# Connector_0.net
KiCad netlist of a schematic drawn in Altium Designer
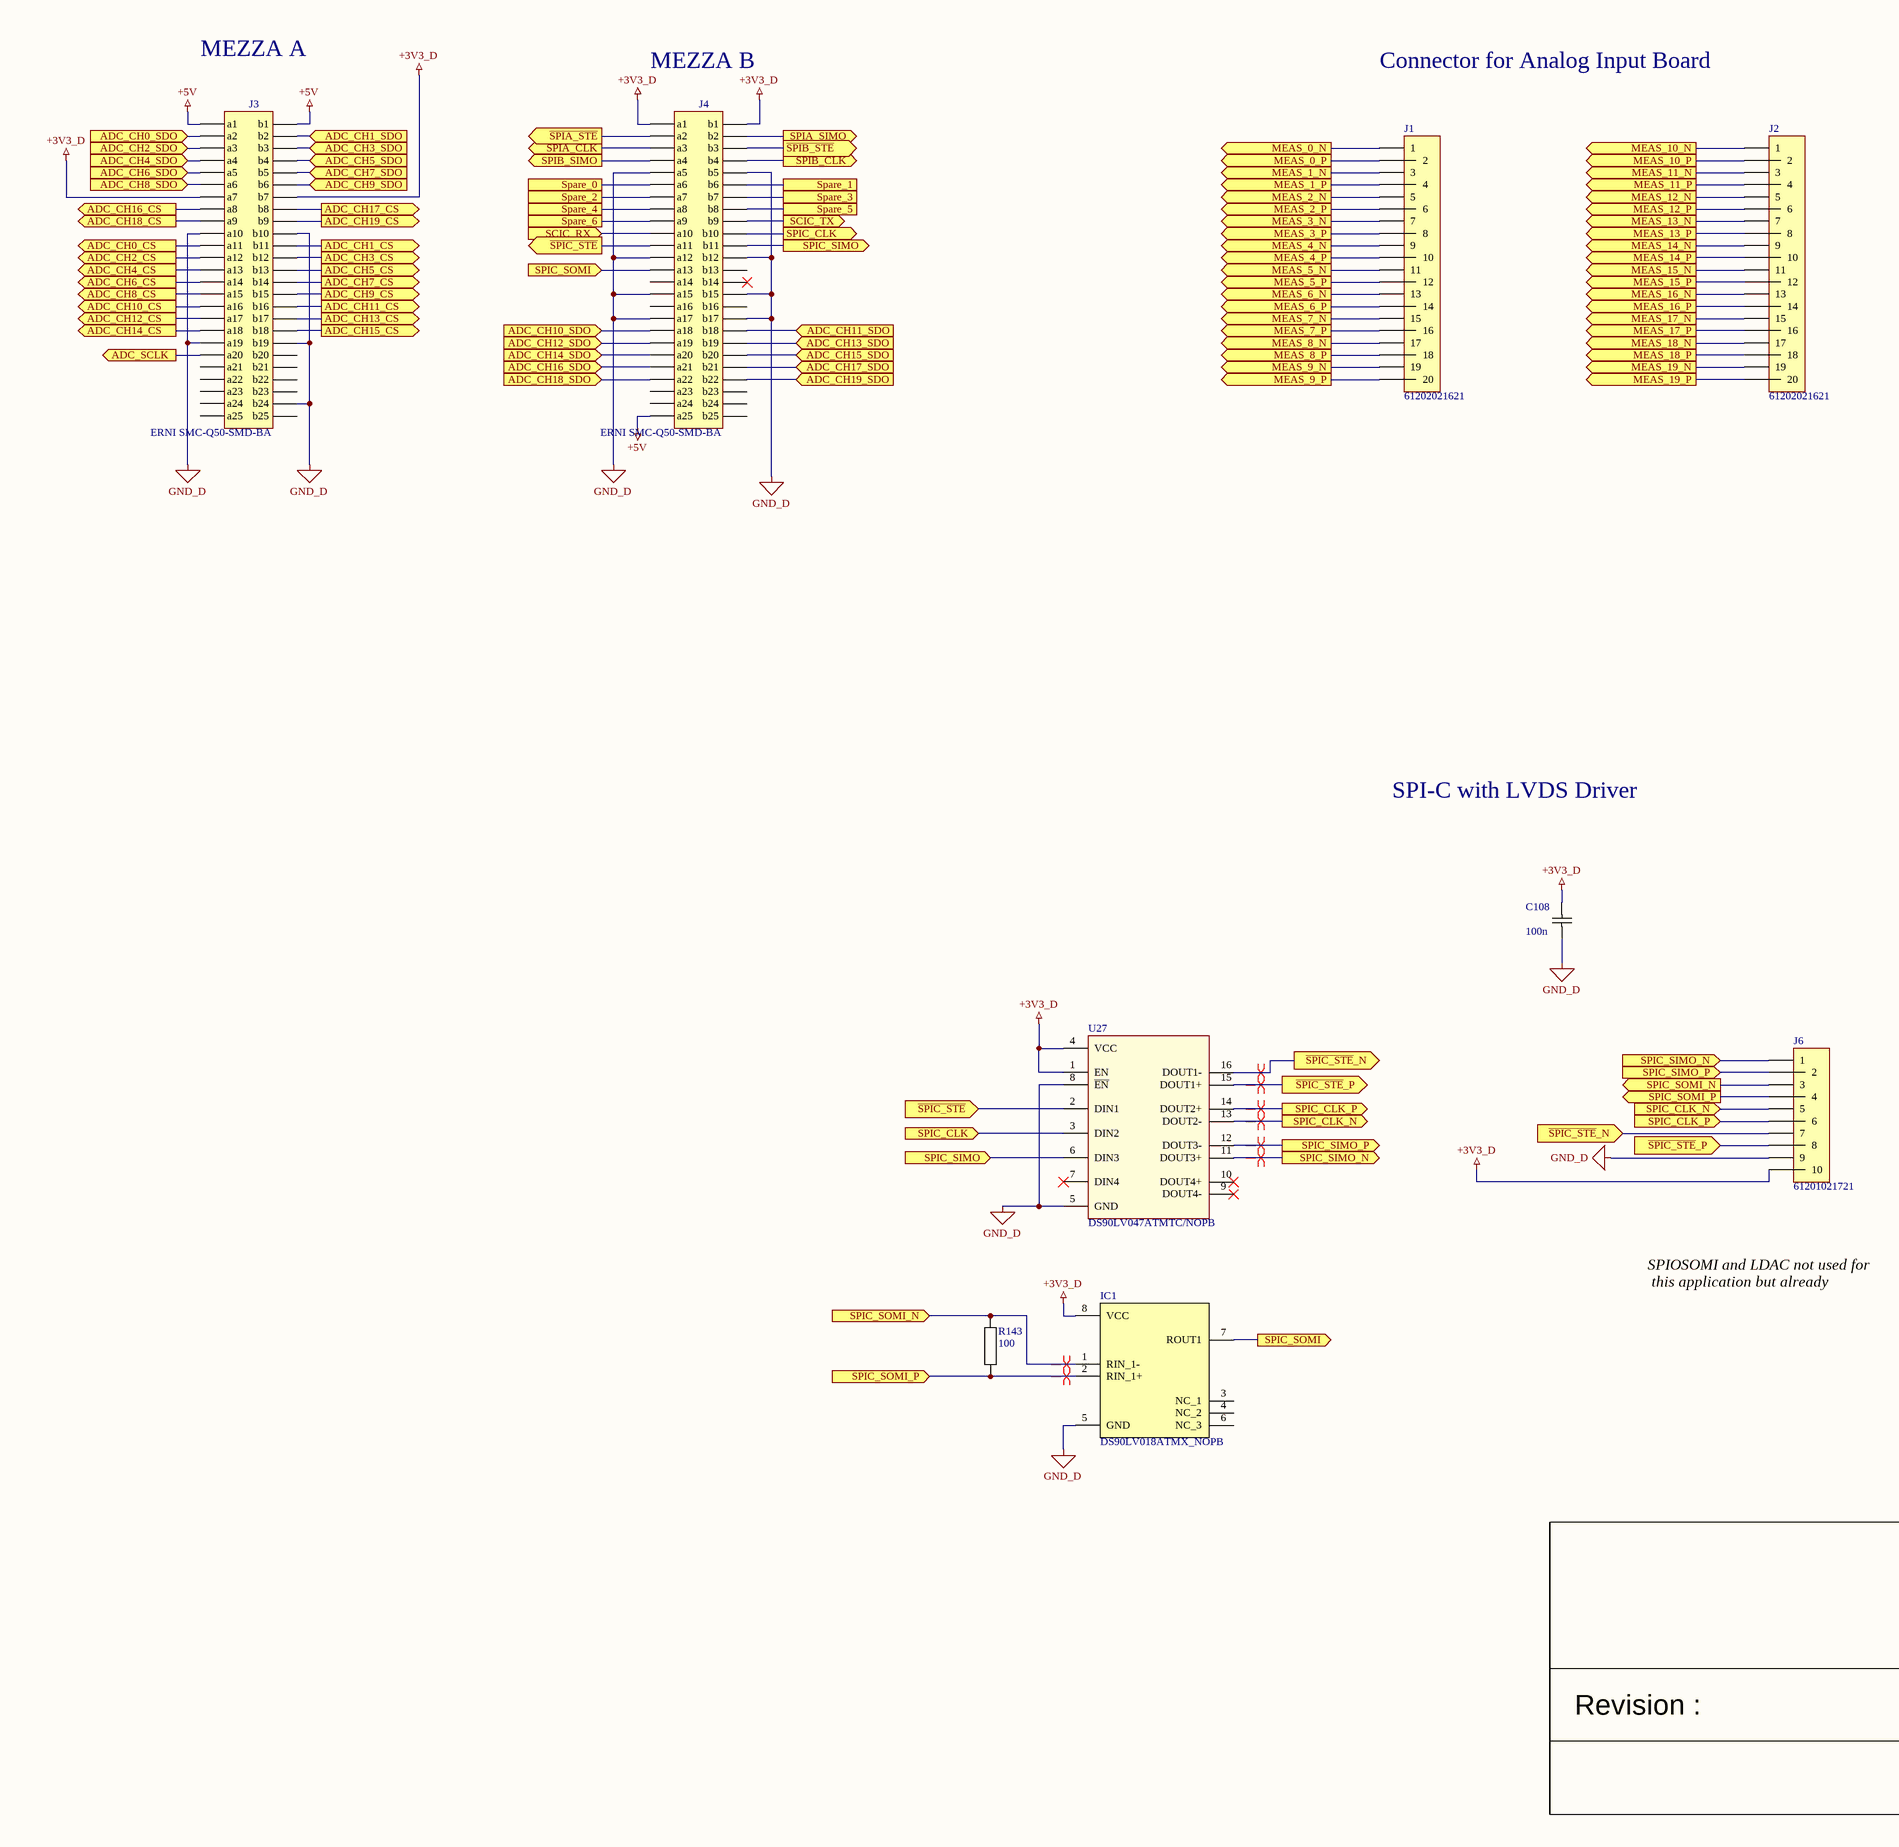
[diagram p0: Connector_0.SchDoc, left]
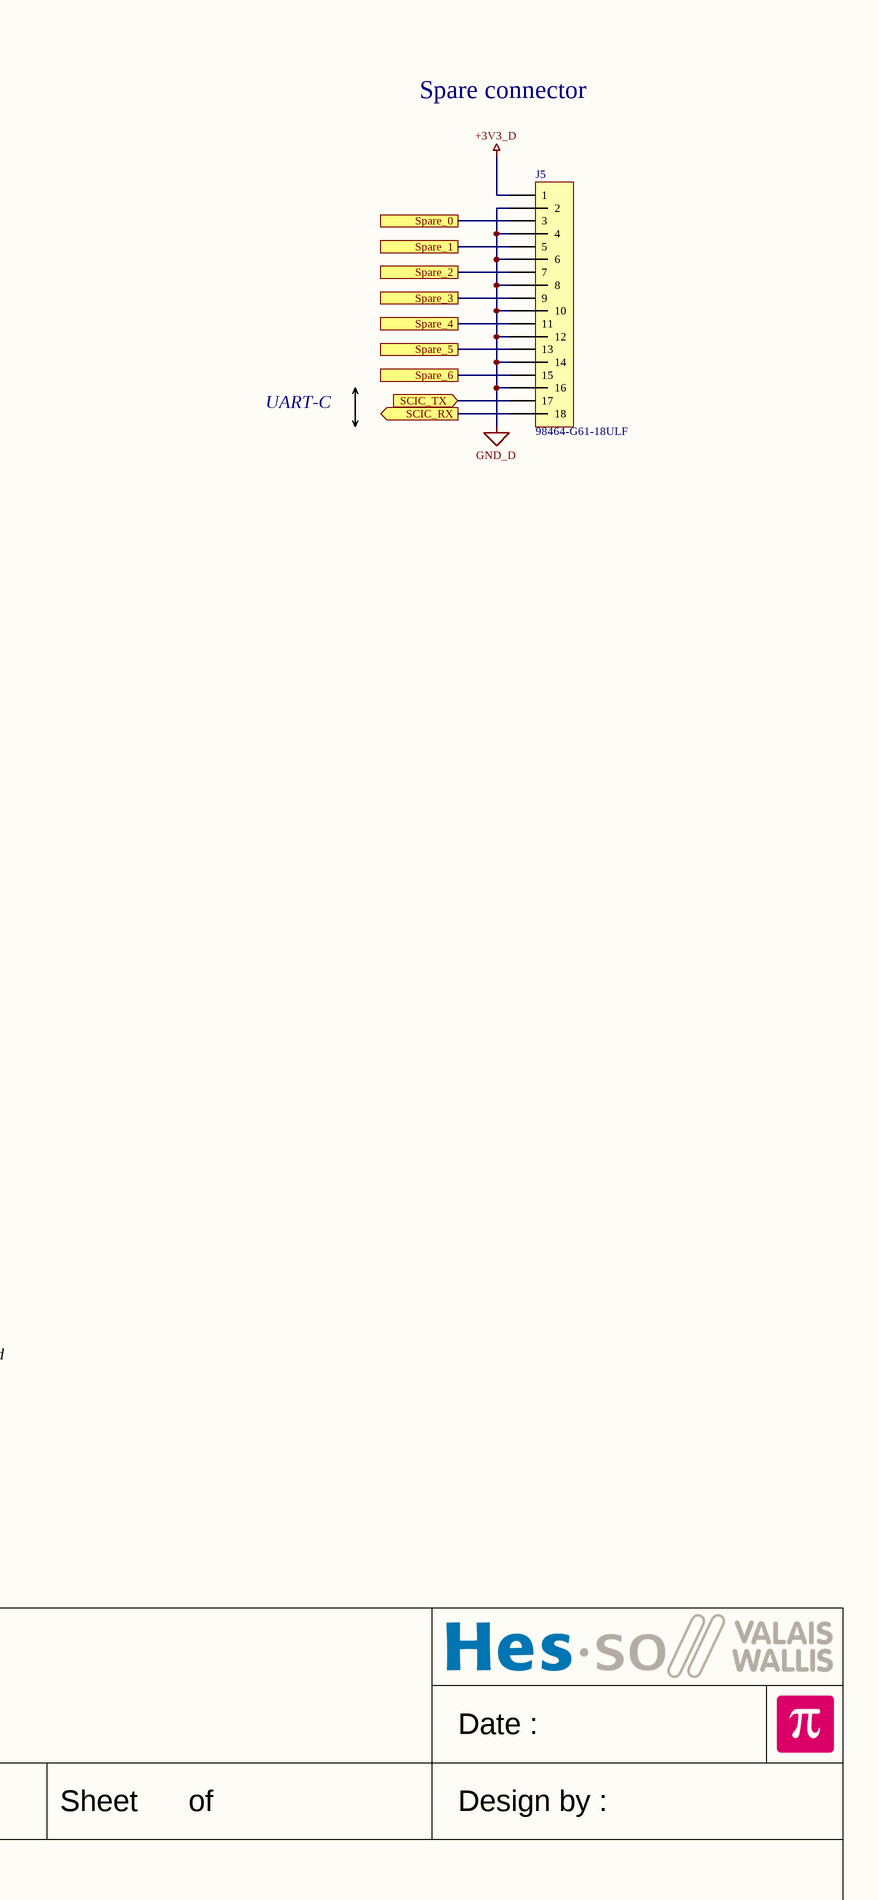
[diagram p1: Connector_0.SchDoc, right]

(export (version "E")
  (design (tool "Eeschema 10.0.6"))
  (components
    (comp (ref "C108")
      (value "100n")
      (footprint "CAPACITOR 2012 REFLOW")
      (description "Capacitor X7R 10% 50V 2012(0805)")
      (libsource (lib "Capacitor") (part "Capacitor"))
    )
    (comp (ref "IC1")
      (value "DS90LV018ATMX_NOPB")
      (footprint "SamacSys:SOIC127P600X175-8N")
      (description "Integrated Circuit")
      (fields
        (field (name "MANUFACTURER_PART_NUMBER") "DS90LV018ATMX/NOPB")
        (field (name "MOUSER PART NUMBER") "926-DS90LV018ATMXNPB")
      )
      (libsource (lib "SamacSys") (part "DS90LV018ATMX_NOPB"))
    )
    (comp (ref "J1")
      (value "61202021621")
      (footprint "FlatCable2x10 2.54MM RIGHT ANGLE TH")
      (description "FlatCable2x10")
      (fields (field (name "MANUFACTURER") "Wurth Elektronik"))
      (libsource (lib "Connector") (part "FlatCable2x10"))
    )
    (comp (ref "J2")
      (value "61202021621")
      (footprint "FlatCable2x10 2.54MM RIGHT ANGLE TH")
      (description "FlatCable2x10")
      (fields (field (name "MANUFACTURER") "Wurth Elektronik"))
      (libsource (lib "Connector") (part "FlatCable2x10"))
    )
    (comp (ref "J3")
      (value "ERNI SMC-Q50-SMD-BA")
      (footprint "ERNI SMC-Q50-SMD-BA")
      (description "Male 1.27 pitch 2x25 pin connector")
      (libsource (lib "Connector") (part "ERNI SMC-Q50-SMD-BA"))
    )
    (comp (ref "J4")
      (value "ERNI SMC-Q50-SMD-BA")
      (footprint "ERNI SMC-Q50-SMD-BA")
      (description "Male 1.27 pitch 2x25 pin connector")
      (libsource (lib "Connector") (part "ERNI SMC-Q50-SMD-BA"))
    )
    (comp (ref "J5")
      (value "98464-G61-18ULF")
      (footprint "FlatCable2x9 2MM Straight SMD FCI 98414-G52-18ALF")
      (description "FlatCable2x9")
      (fields (field (name "MANUFACTURER") "Amphenol FCI"))
      (libsource (lib "Connector") (part "FlatCable2x9"))
    )
    (comp (ref "J6")
      (value "61201021721")
      (footprint "FlatCable2x5 2.54MM Straight TH")
      (description "FlatCable2x5")
      (fields (field (name "MANUFACTURER") "Wurth Elektronik"))
      (libsource (lib "Connector") (part "FlatCable2x5"))
    )
    (comp (ref "R143")
      (value "100")
      (footprint "RESISTOR 1608 REFLOW")
      (description "Resistor 1% 50V 100mW 1608(0603)")
      (libsource (lib "Resistor") (part "Resistor"))
    )
    (comp (ref "U27")
      (value "DS90LV047ATMTC/NOPB")
      (footprint "TSSOP16 P0.65 C5.0x4.5 H1.1")
      (description "DS90LV047A 3-V LVDS Quad CMOS Differential Line Driver")
      (fields (field (name "MANUFACTURER") "Texas Instruments"))
      (libsource (lib "IntegratedCircuit") (part "DS90LV047A"))
    )
  )
  (nets
    (net (code "1") (name "+3V3_D") (class "Default")
      (node (ref "C108") (pin "2") (pinfunction "2_2") (pintype "passive"))
      (node (ref "IC1") (pin "8") (pinfunction "VCC_8") (pintype "passive"))
      (node (ref "J3") (pin "a7") (pinfunction "a7_a7") (pintype "passive"))
      (node (ref "J3") (pin "b7") (pinfunction "b7_b7") (pintype "passive"))
      (node (ref "J4") (pin "a1") (pinfunction "a1_a1") (pintype "passive"))
      (node (ref "J4") (pin "b1") (pinfunction "b1_b1") (pintype "passive"))
      (node (ref "J5") (pin "1") (pinfunction "1_1") (pintype "passive"))
      (node (ref "J6") (pin "10") (pinfunction "10_10") (pintype "passive"))
      (node (ref "U27") (pin "1") (pinfunction "EN_1") (pintype "passive"))
      (node (ref "U27") (pin "4") (pinfunction "VCC_4") (pintype "passive"))
    )
    (net (code "2") (name "+5V") (class "Default")
      (node (ref "J3") (pin "a1") (pinfunction "a1_a1") (pintype "passive"))
      (node (ref "J3") (pin "b1") (pinfunction "b1_b1") (pintype "passive"))
      (node (ref "J4") (pin "a25") (pinfunction "a25_a25") (pintype "passive"))
    )
    (net (code "3") (name "/ADC_CH0_CS") (class "Default")
      (node (ref "J3") (pin "a11") (pinfunction "a11_a11") (pintype "passive"))
    )
    (net (code "4") (name "/ADC_CH0_SDO") (class "Default")
      (node (ref "J3") (pin "a2") (pinfunction "a2_a2") (pintype "passive"))
    )
    (net (code "5") (name "/ADC_CH1_CS") (class "Default")
      (node (ref "J3") (pin "b11") (pinfunction "b11_b11") (pintype "passive"))
    )
    (net (code "6") (name "/ADC_CH1_SDO") (class "Default")
      (node (ref "J3") (pin "b2") (pinfunction "b2_b2") (pintype "passive"))
    )
    (net (code "7") (name "/ADC_CH2_CS") (class "Default")
      (node (ref "J3") (pin "a12") (pinfunction "a12_a12") (pintype "passive"))
    )
    (net (code "8") (name "/ADC_CH2_SDO") (class "Default")
      (node (ref "J3") (pin "a3") (pinfunction "a3_a3") (pintype "passive"))
    )
    (net (code "9") (name "/ADC_CH3_CS") (class "Default")
      (node (ref "J3") (pin "b12") (pinfunction "b12_b12") (pintype "passive"))
    )
    (net (code "10") (name "/ADC_CH3_SDO") (class "Default")
      (node (ref "J3") (pin "b3") (pinfunction "b3_b3") (pintype "passive"))
    )
    (net (code "11") (name "/ADC_CH4_CS") (class "Default")
      (node (ref "J3") (pin "a13") (pinfunction "a13_a13") (pintype "passive"))
    )
    (net (code "12") (name "/ADC_CH4_SDO") (class "Default")
      (node (ref "J3") (pin "a4") (pinfunction "a4_a4") (pintype "passive"))
    )
    (net (code "13") (name "/ADC_CH5_CS") (class "Default")
      (node (ref "J3") (pin "b13") (pinfunction "b13_b13") (pintype "passive"))
    )
    (net (code "14") (name "/ADC_CH5_SDO") (class "Default")
      (node (ref "J3") (pin "b4") (pinfunction "b4_b4") (pintype "passive"))
    )
    (net (code "15") (name "/ADC_CH6_CS") (class "Default")
      (node (ref "J3") (pin "a14") (pinfunction "a14_a14") (pintype "passive"))
    )
    (net (code "16") (name "/ADC_CH6_SDO") (class "Default")
      (node (ref "J3") (pin "a5") (pinfunction "a5_a5") (pintype "passive"))
    )
    (net (code "17") (name "/ADC_CH7_CS") (class "Default")
      (node (ref "J3") (pin "b14") (pinfunction "b14_b14") (pintype "passive"))
    )
    (net (code "18") (name "/ADC_CH7_SDO") (class "Default")
      (node (ref "J3") (pin "b5") (pinfunction "b5_b5") (pintype "passive"))
    )
    (net (code "19") (name "/ADC_CH8_CS") (class "Default")
      (node (ref "J3") (pin "a15") (pinfunction "a15_a15") (pintype "passive"))
    )
    (net (code "20") (name "/ADC_CH8_SDO") (class "Default")
      (node (ref "J3") (pin "a6") (pinfunction "a6_a6") (pintype "passive"))
    )
    (net (code "21") (name "/ADC_CH9_CS") (class "Default")
      (node (ref "J3") (pin "b15") (pinfunction "b15_b15") (pintype "passive"))
    )
    (net (code "22") (name "/ADC_CH9_SDO") (class "Default")
      (node (ref "J3") (pin "b6") (pinfunction "b6_b6") (pintype "passive"))
    )
    (net (code "23") (name "/ADC_CH10_CS") (class "Default")
      (node (ref "J3") (pin "a16") (pinfunction "a16_a16") (pintype "passive"))
    )
    (net (code "24") (name "/ADC_CH10_SDO") (class "Default")
      (node (ref "J4") (pin "a18") (pinfunction "a18_a18") (pintype "passive"))
    )
    (net (code "25") (name "/ADC_CH11_CS") (class "Default")
      (node (ref "J3") (pin "b16") (pinfunction "b16_b16") (pintype "passive"))
    )
    (net (code "26") (name "/ADC_CH11_SDO") (class "Default")
      (node (ref "J4") (pin "b18") (pinfunction "b18_b18") (pintype "passive"))
    )
    (net (code "27") (name "/ADC_CH12_CS") (class "Default")
      (node (ref "J3") (pin "a17") (pinfunction "a17_a17") (pintype "passive"))
    )
    (net (code "28") (name "/ADC_CH12_SDO") (class "Default")
      (node (ref "J4") (pin "a19") (pinfunction "a19_a19") (pintype "passive"))
    )
    (net (code "29") (name "/ADC_CH13_CS") (class "Default")
      (node (ref "J3") (pin "b17") (pinfunction "b17_b17") (pintype "passive"))
    )
    (net (code "30") (name "/ADC_CH13_SDO") (class "Default")
      (node (ref "J4") (pin "b19") (pinfunction "b19_b19") (pintype "passive"))
    )
    (net (code "31") (name "/ADC_CH14_CS") (class "Default")
      (node (ref "J3") (pin "a18") (pinfunction "a18_a18") (pintype "passive"))
    )
    (net (code "32") (name "/ADC_CH14_SDO") (class "Default")
      (node (ref "J4") (pin "a20") (pinfunction "a20_a20") (pintype "passive"))
    )
    (net (code "33") (name "/ADC_CH15_CS") (class "Default")
      (node (ref "J3") (pin "b18") (pinfunction "b18_b18") (pintype "passive"))
    )
    (net (code "34") (name "/ADC_CH15_SDO") (class "Default")
      (node (ref "J4") (pin "b20") (pinfunction "b20_b20") (pintype "passive"))
    )
    (net (code "35") (name "/ADC_CH16_CS") (class "Default")
      (node (ref "J3") (pin "a8") (pinfunction "a8_a8") (pintype "passive"))
    )
    (net (code "36") (name "/ADC_CH16_SDO") (class "Default")
      (node (ref "J4") (pin "a21") (pinfunction "a21_a21") (pintype "passive"))
    )
    (net (code "37") (name "/ADC_CH17_CS") (class "Default")
      (node (ref "J3") (pin "b8") (pinfunction "b8_b8") (pintype "passive"))
    )
    (net (code "38") (name "/ADC_CH17_SDO") (class "Default")
      (node (ref "J4") (pin "b21") (pinfunction "b21_b21") (pintype "passive"))
    )
    (net (code "39") (name "/ADC_CH18_CS") (class "Default")
      (node (ref "J3") (pin "a9") (pinfunction "a9_a9") (pintype "passive"))
    )
    (net (code "40") (name "/ADC_CH18_SDO") (class "Default")
      (node (ref "J4") (pin "a22") (pinfunction "a22_a22") (pintype "passive"))
    )
    (net (code "41") (name "/ADC_CH19_CS") (class "Default")
      (node (ref "J3") (pin "b9") (pinfunction "b9_b9") (pintype "passive"))
    )
    (net (code "42") (name "/ADC_CH19_SDO") (class "Default")
      (node (ref "J4") (pin "b22") (pinfunction "b22_b22") (pintype "passive"))
    )
    (net (code "43") (name "/ADC_SCLK") (class "Default")
      (node (ref "J3") (pin "a20") (pinfunction "a20_a20") (pintype "passive"))
    )
    (net (code "44") (name "/MEAS_0_N") (class "Default")
      (node (ref "J1") (pin "1") (pinfunction "1_1") (pintype "passive"))
    )
    (net (code "45") (name "/MEAS_0_P") (class "Default")
      (node (ref "J1") (pin "2") (pinfunction "2_2") (pintype "passive"))
    )
    (net (code "46") (name "/MEAS_1_N") (class "Default")
      (node (ref "J1") (pin "3") (pinfunction "3_3") (pintype "passive"))
    )
    (net (code "47") (name "/MEAS_1_P") (class "Default")
      (node (ref "J1") (pin "4") (pinfunction "4_4") (pintype "passive"))
    )
    (net (code "48") (name "/MEAS_2_N") (class "Default")
      (node (ref "J1") (pin "5") (pinfunction "5_5") (pintype "passive"))
    )
    (net (code "49") (name "/MEAS_2_P") (class "Default")
      (node (ref "J1") (pin "6") (pinfunction "6_6") (pintype "passive"))
    )
    (net (code "50") (name "/MEAS_3_N") (class "Default")
      (node (ref "J1") (pin "7") (pinfunction "7_7") (pintype "passive"))
    )
    (net (code "51") (name "/MEAS_3_P") (class "Default")
      (node (ref "J1") (pin "8") (pinfunction "8_8") (pintype "passive"))
    )
    (net (code "52") (name "/MEAS_4_N") (class "Default")
      (node (ref "J1") (pin "9") (pinfunction "9_9") (pintype "passive"))
    )
    (net (code "53") (name "/MEAS_4_P") (class "Default")
      (node (ref "J1") (pin "10") (pinfunction "10_10") (pintype "passive"))
    )
    (net (code "54") (name "/MEAS_5_N") (class "Default")
      (node (ref "J1") (pin "11") (pinfunction "11_11") (pintype "passive"))
    )
    (net (code "55") (name "/MEAS_5_P") (class "Default")
      (node (ref "J1") (pin "12") (pinfunction "12_12") (pintype "passive"))
    )
    (net (code "56") (name "/MEAS_6_N") (class "Default")
      (node (ref "J1") (pin "13") (pinfunction "13_13") (pintype "passive"))
    )
    (net (code "57") (name "/MEAS_6_P") (class "Default")
      (node (ref "J1") (pin "14") (pinfunction "14_14") (pintype "passive"))
    )
    (net (code "58") (name "/MEAS_7_N") (class "Default")
      (node (ref "J1") (pin "15") (pinfunction "15_15") (pintype "passive"))
    )
    (net (code "59") (name "/MEAS_7_P") (class "Default")
      (node (ref "J1") (pin "16") (pinfunction "16_16") (pintype "passive"))
    )
    (net (code "60") (name "/MEAS_8_N") (class "Default")
      (node (ref "J1") (pin "17") (pinfunction "17_17") (pintype "passive"))
    )
    (net (code "61") (name "/MEAS_8_P") (class "Default")
      (node (ref "J1") (pin "18") (pinfunction "18_18") (pintype "passive"))
    )
    (net (code "62") (name "/MEAS_9_N") (class "Default")
      (node (ref "J1") (pin "19") (pinfunction "19_19") (pintype "passive"))
    )
    (net (code "63") (name "/MEAS_9_P") (class "Default")
      (node (ref "J1") (pin "20") (pinfunction "20_20") (pintype "passive"))
    )
    (net (code "64") (name "/MEAS_10_N") (class "Default")
      (node (ref "J2") (pin "1") (pinfunction "1_1") (pintype "passive"))
    )
    (net (code "65") (name "/MEAS_10_P") (class "Default")
      (node (ref "J2") (pin "2") (pinfunction "2_2") (pintype "passive"))
    )
    (net (code "66") (name "/MEAS_11_N") (class "Default")
      (node (ref "J2") (pin "3") (pinfunction "3_3") (pintype "passive"))
    )
    (net (code "67") (name "/MEAS_11_P") (class "Default")
      (node (ref "J2") (pin "4") (pinfunction "4_4") (pintype "passive"))
    )
    (net (code "68") (name "/MEAS_12_N") (class "Default")
      (node (ref "J2") (pin "5") (pinfunction "5_5") (pintype "passive"))
    )
    (net (code "69") (name "/MEAS_12_P") (class "Default")
      (node (ref "J2") (pin "6") (pinfunction "6_6") (pintype "passive"))
    )
    (net (code "70") (name "/MEAS_13_N") (class "Default")
      (node (ref "J2") (pin "7") (pinfunction "7_7") (pintype "passive"))
    )
    (net (code "71") (name "/MEAS_13_P") (class "Default")
      (node (ref "J2") (pin "8") (pinfunction "8_8") (pintype "passive"))
    )
    (net (code "72") (name "/MEAS_14_N") (class "Default")
      (node (ref "J2") (pin "9") (pinfunction "9_9") (pintype "passive"))
    )
    (net (code "73") (name "/MEAS_14_P") (class "Default")
      (node (ref "J2") (pin "10") (pinfunction "10_10") (pintype "passive"))
    )
    (net (code "74") (name "/MEAS_15_N") (class "Default")
      (node (ref "J2") (pin "11") (pinfunction "11_11") (pintype "passive"))
    )
    (net (code "75") (name "/MEAS_15_P") (class "Default")
      (node (ref "J2") (pin "12") (pinfunction "12_12") (pintype "passive"))
    )
    (net (code "76") (name "/MEAS_16_N") (class "Default")
      (node (ref "J2") (pin "13") (pinfunction "13_13") (pintype "passive"))
    )
    (net (code "77") (name "/MEAS_16_P") (class "Default")
      (node (ref "J2") (pin "14") (pinfunction "14_14") (pintype "passive"))
    )
    (net (code "78") (name "/MEAS_17_N") (class "Default")
      (node (ref "J2") (pin "15") (pinfunction "15_15") (pintype "passive"))
    )
    (net (code "79") (name "/MEAS_17_P") (class "Default")
      (node (ref "J2") (pin "16") (pinfunction "16_16") (pintype "passive"))
    )
    (net (code "80") (name "/MEAS_18_N") (class "Default")
      (node (ref "J2") (pin "17") (pinfunction "17_17") (pintype "passive"))
    )
    (net (code "81") (name "/MEAS_18_P") (class "Default")
      (node (ref "J2") (pin "18") (pinfunction "18_18") (pintype "passive"))
    )
    (net (code "82") (name "/MEAS_19_N") (class "Default")
      (node (ref "J2") (pin "19") (pinfunction "19_19") (pintype "passive"))
    )
    (net (code "83") (name "/MEAS_19_P") (class "Default")
      (node (ref "J2") (pin "20") (pinfunction "20_20") (pintype "passive"))
    )
    (net (code "84") (name "/SCIC_RX") (class "Default")
      (node (ref "J4") (pin "a10") (pinfunction "a10_a10") (pintype "passive"))
      (node (ref "J5") (pin "18") (pinfunction "18_18") (pintype "passive"))
    )
    (net (code "85") (name "/SCIC_TX") (class "Default")
      (node (ref "J4") (pin "b9") (pinfunction "b9_b9") (pintype "passive"))
      (node (ref "J5") (pin "17") (pinfunction "17_17") (pintype "passive"))
    )
    (net (code "86") (name "/SPIA_CLK") (class "Default")
      (node (ref "J4") (pin "a3") (pinfunction "a3_a3") (pintype "passive"))
    )
    (net (code "87") (name "/SPIA_SIMO") (class "Default")
      (node (ref "J4") (pin "b2") (pinfunction "b2_b2") (pintype "passive"))
    )
    (net (code "88") (name "/SPIB_CLK") (class "Default")
      (node (ref "J4") (pin "b4") (pinfunction "b4_b4") (pintype "passive"))
    )
    (net (code "89") (name "/SPIB_SIMO") (class "Default")
      (node (ref "J4") (pin "a4") (pinfunction "a4_a4") (pintype "passive"))
    )
    (net (code "90") (name "/SPIC_CLK") (class "Default")
      (node (ref "J4") (pin "b10") (pinfunction "b10_b10") (pintype "passive"))
      (node (ref "U27") (pin "3") (pinfunction "DIN2_3") (pintype "passive"))
    )
    (net (code "91") (name "/SPIC_CLK_N") (class "Default")
      (node (ref "J6") (pin "5") (pinfunction "5_5") (pintype "passive"))
      (node (ref "U27") (pin "13") (pinfunction "DOUT2-_13") (pintype "passive"))
    )
    (net (code "92") (name "/SPIC_CLK_P") (class "Default")
      (node (ref "J6") (pin "6") (pinfunction "6_6") (pintype "passive"))
      (node (ref "U27") (pin "14") (pinfunction "DOUT2+_14") (pintype "passive"))
    )
    (net (code "93") (name "/SPIC_SIMO") (class "Default")
      (node (ref "J4") (pin "b11") (pinfunction "b11_b11") (pintype "passive"))
      (node (ref "U27") (pin "6") (pinfunction "DIN3_6") (pintype "passive"))
    )
    (net (code "94") (name "/SPIC_SIMO_N") (class "Default")
      (node (ref "J6") (pin "1") (pinfunction "1_1") (pintype "passive"))
      (node (ref "U27") (pin "11") (pinfunction "DOUT3+_11") (pintype "passive"))
    )
    (net (code "95") (name "/SPIC_SIMO_P") (class "Default")
      (node (ref "J6") (pin "2") (pinfunction "2_2") (pintype "passive"))
      (node (ref "U27") (pin "12") (pinfunction "DOUT3-_12") (pintype "passive"))
    )
    (net (code "96") (name "/SPIC_SOMI") (class "Default")
      (node (ref "IC1") (pin "7") (pinfunction "ROUT1_7") (pintype "passive"))
      (node (ref "J4") (pin "a13") (pinfunction "a13_a13") (pintype "passive"))
    )
    (net (code "97") (name "/SPIC_SOMI_N") (class "Default")
      (node (ref "IC1") (pin "1") (pinfunction "RIN_1-_1") (pintype "passive"))
      (node (ref "J6") (pin "3") (pinfunction "3_3") (pintype "passive"))
      (node (ref "R143") (pin "1") (pinfunction "1_1") (pintype "passive"))
    )
    (net (code "98") (name "/SPIC_SOMI_P") (class "Default")
      (node (ref "IC1") (pin "2") (pinfunction "RIN_1+_2") (pintype "passive"))
      (node (ref "J6") (pin "4") (pinfunction "4_4") (pintype "passive"))
      (node (ref "R143") (pin "2") (pinfunction "2_2") (pintype "passive"))
    )
    (net (code "99") (name "/Spare_0") (class "Default")
      (node (ref "J4") (pin "a6") (pinfunction "a6_a6") (pintype "passive"))
      (node (ref "J5") (pin "3") (pinfunction "3_3") (pintype "passive"))
    )
    (net (code "100") (name "/Spare_1") (class "Default")
      (node (ref "J4") (pin "b6") (pinfunction "b6_b6") (pintype "passive"))
      (node (ref "J5") (pin "5") (pinfunction "5_5") (pintype "passive"))
    )
    (net (code "101") (name "/Spare_2") (class "Default")
      (node (ref "J4") (pin "a7") (pinfunction "a7_a7") (pintype "passive"))
      (node (ref "J5") (pin "7") (pinfunction "7_7") (pintype "passive"))
    )
    (net (code "102") (name "/Spare_3") (class "Default")
      (node (ref "J4") (pin "b7") (pinfunction "b7_b7") (pintype "passive"))
      (node (ref "J5") (pin "9") (pinfunction "9_9") (pintype "passive"))
    )
    (net (code "103") (name "/Spare_4") (class "Default")
      (node (ref "J4") (pin "a8") (pinfunction "a8_a8") (pintype "passive"))
      (node (ref "J5") (pin "11") (pinfunction "11_11") (pintype "passive"))
    )
    (net (code "104") (name "/Spare_5") (class "Default")
      (node (ref "J4") (pin "b8") (pinfunction "b8_b8") (pintype "passive"))
      (node (ref "J5") (pin "13") (pinfunction "13_13") (pintype "passive"))
    )
    (net (code "105") (name "/Spare_6") (class "Default")
      (node (ref "J4") (pin "a9") (pinfunction "a9_a9") (pintype "passive"))
      (node (ref "J5") (pin "15") (pinfunction "15_15") (pintype "passive"))
    )
    (net (code "106") (name "/~{SPIA_STE}") (class "Default")
      (node (ref "J4") (pin "a2") (pinfunction "a2_a2") (pintype "passive"))
    )
    (net (code "107") (name "/~{SPIB_STE}") (class "Default")
      (node (ref "J4") (pin "b3") (pinfunction "b3_b3") (pintype "passive"))
    )
    (net (code "108") (name "/~{SPIC_STE}") (class "Default")
      (node (ref "J4") (pin "a11") (pinfunction "a11_a11") (pintype "passive"))
      (node (ref "U27") (pin "2") (pinfunction "DIN1_2") (pintype "passive"))
    )
    (net (code "109") (name "/~{SPIC_STE}_N") (class "Default")
      (node (ref "J6") (pin "7") (pinfunction "7_7") (pintype "passive"))
      (node (ref "U27") (pin "16") (pinfunction "DOUT1-_16") (pintype "passive"))
    )
    (net (code "110") (name "/~{SPIC_STE}_P") (class "Default")
      (node (ref "J6") (pin "8") (pinfunction "8_8") (pintype "passive"))
      (node (ref "U27") (pin "15") (pinfunction "DOUT1+_15") (pintype "passive"))
    )
    (net (code "111") (name "GND_D") (class "Default")
      (node (ref "C108") (pin "1") (pinfunction "1_1") (pintype "passive"))
      (node (ref "IC1") (pin "5") (pinfunction "GND_5") (pintype "passive"))
      (node (ref "J3") (pin "a10") (pinfunction "a10_a10") (pintype "passive"))
      (node (ref "J3") (pin "a19") (pinfunction "a19_a19") (pintype "passive"))
      (node (ref "J3") (pin "b10") (pinfunction "b10_b10") (pintype "passive"))
      (node (ref "J3") (pin "b19") (pinfunction "b19_b19") (pintype "passive"))
      (node (ref "J3") (pin "b24") (pinfunction "b24_b24") (pintype "passive"))
      (node (ref "J4") (pin "a12") (pinfunction "a12_a12") (pintype "passive"))
      (node (ref "J4") (pin "a15") (pinfunction "a15_a15") (pintype "passive"))
      (node (ref "J4") (pin "a17") (pinfunction "a17_a17") (pintype "passive"))
      (node (ref "J4") (pin "a5") (pinfunction "a5_a5") (pintype "passive"))
      (node (ref "J4") (pin "b12") (pinfunction "b12_b12") (pintype "passive"))
      (node (ref "J4") (pin "b15") (pinfunction "b15_b15") (pintype "passive"))
      (node (ref "J4") (pin "b17") (pinfunction "b17_b17") (pintype "passive"))
      (node (ref "J4") (pin "b5") (pinfunction "b5_b5") (pintype "passive"))
      (node (ref "J5") (pin "10") (pinfunction "10_10") (pintype "passive"))
      (node (ref "J5") (pin "12") (pinfunction "12_12") (pintype "passive"))
      (node (ref "J5") (pin "14") (pinfunction "14_14") (pintype "passive"))
      (node (ref "J5") (pin "16") (pinfunction "16_16") (pintype "passive"))
      (node (ref "J5") (pin "2") (pinfunction "2_2") (pintype "passive"))
      (node (ref "J5") (pin "4") (pinfunction "4_4") (pintype "passive"))
      (node (ref "J5") (pin "6") (pinfunction "6_6") (pintype "passive"))
      (node (ref "J5") (pin "8") (pinfunction "8_8") (pintype "passive"))
      (node (ref "J6") (pin "9") (pinfunction "9_9") (pintype "passive"))
      (node (ref "U27") (pin "5") (pinfunction "GND_5") (pintype "passive"))
      (node (ref "U27") (pin "8") (pinfunction "~{EN}_8") (pintype "passive"))
    )
    (net (code "112") (name "unconnected-(IC1-NC_1-Pad3)") (class "Default")
      (node (ref "IC1") (pin "3") (pinfunction "NC_1_3") (pintype "passive"))
    )
    (net (code "113") (name "unconnected-(IC1-NC_2-Pad4)") (class "Default")
      (node (ref "IC1") (pin "4") (pinfunction "NC_2_4") (pintype "passive"))
    )
    (net (code "114") (name "unconnected-(IC1-NC_3-Pad6)") (class "Default")
      (node (ref "IC1") (pin "6") (pinfunction "NC_3_6") (pintype "passive"))
    )
    (net (code "115") (name "unconnected-(J3-Pada21)") (class "Default")
      (node (ref "J3") (pin "a21") (pinfunction "a21_a21") (pintype "passive"))
    )
    (net (code "116") (name "unconnected-(J3-Pada22)") (class "Default")
      (node (ref "J3") (pin "a22") (pinfunction "a22_a22") (pintype "passive"))
    )
    (net (code "117") (name "unconnected-(J3-Pada23)") (class "Default")
      (node (ref "J3") (pin "a23") (pinfunction "a23_a23") (pintype "passive"))
    )
    (net (code "118") (name "unconnected-(J3-Pada24)") (class "Default")
      (node (ref "J3") (pin "a24") (pinfunction "a24_a24") (pintype "passive"))
    )
    (net (code "119") (name "unconnected-(J3-Pada25)") (class "Default")
      (node (ref "J3") (pin "a25") (pinfunction "a25_a25") (pintype "passive"))
    )
    (net (code "120") (name "unconnected-(J3-Padb20)") (class "Default")
      (node (ref "J3") (pin "b20") (pinfunction "b20_b20") (pintype "passive"))
    )
    (net (code "121") (name "unconnected-(J3-Padb21)") (class "Default")
      (node (ref "J3") (pin "b21") (pinfunction "b21_b21") (pintype "passive"))
    )
    (net (code "122") (name "unconnected-(J3-Padb22)") (class "Default")
      (node (ref "J3") (pin "b22") (pinfunction "b22_b22") (pintype "passive"))
    )
    (net (code "123") (name "unconnected-(J3-Padb23)") (class "Default")
      (node (ref "J3") (pin "b23") (pinfunction "b23_b23") (pintype "passive"))
    )
    (net (code "124") (name "unconnected-(J3-Padb25)") (class "Default")
      (node (ref "J3") (pin "b25") (pinfunction "b25_b25") (pintype "passive"))
    )
    (net (code "125") (name "unconnected-(J4-Pada14)") (class "Default")
      (node (ref "J4") (pin "a14") (pinfunction "a14_a14") (pintype "passive"))
    )
    (net (code "126") (name "unconnected-(J4-Pada16)") (class "Default")
      (node (ref "J4") (pin "a16") (pinfunction "a16_a16") (pintype "passive"))
    )
    (net (code "127") (name "unconnected-(J4-Pada23)") (class "Default")
      (node (ref "J4") (pin "a23") (pinfunction "a23_a23") (pintype "passive"))
    )
    (net (code "128") (name "unconnected-(J4-Pada24)") (class "Default")
      (node (ref "J4") (pin "a24") (pinfunction "a24_a24") (pintype "passive"))
    )
    (net (code "129") (name "unconnected-(J4-Padb13)") (class "Default")
      (node (ref "J4") (pin "b13") (pinfunction "b13_b13") (pintype "passive"))
    )
    (net (code "130") (name "unconnected-(J4-Padb14)") (class "Default")
      (node (ref "J4") (pin "b14") (pinfunction "b14_b14") (pintype "passive+no_connect"))
    )
    (net (code "131") (name "unconnected-(J4-Padb16)") (class "Default")
      (node (ref "J4") (pin "b16") (pinfunction "b16_b16") (pintype "passive"))
    )
    (net (code "132") (name "unconnected-(J4-Padb23)") (class "Default")
      (node (ref "J4") (pin "b23") (pinfunction "b23_b23") (pintype "passive"))
    )
    (net (code "133") (name "unconnected-(J4-Padb24)") (class "Default")
      (node (ref "J4") (pin "b24") (pinfunction "b24_b24") (pintype "passive"))
    )
    (net (code "134") (name "unconnected-(J4-Padb25)") (class "Default")
      (node (ref "J4") (pin "b25") (pinfunction "b25_b25") (pintype "passive"))
    )
    (net (code "135") (name "unconnected-(U27-DIN4-Pad7)") (class "Default")
      (node (ref "U27") (pin "7") (pinfunction "DIN4_7") (pintype "passive+no_connect"))
    )
    (net (code "136") (name "unconnected-(U27-DOUT4+-Pad10)") (class "Default")
      (node (ref "U27") (pin "10") (pinfunction "DOUT4+_10") (pintype "passive+no_connect"))
    )
    (net (code "137") (name "unconnected-(U27-DOUT4--Pad9)") (class "Default")
      (node (ref "U27") (pin "9") (pinfunction "DOUT4-_9") (pintype "passive+no_connect"))
    )
  )
)
